# RDN.net
KiCad netlist of a schematic drawn in EAGLE
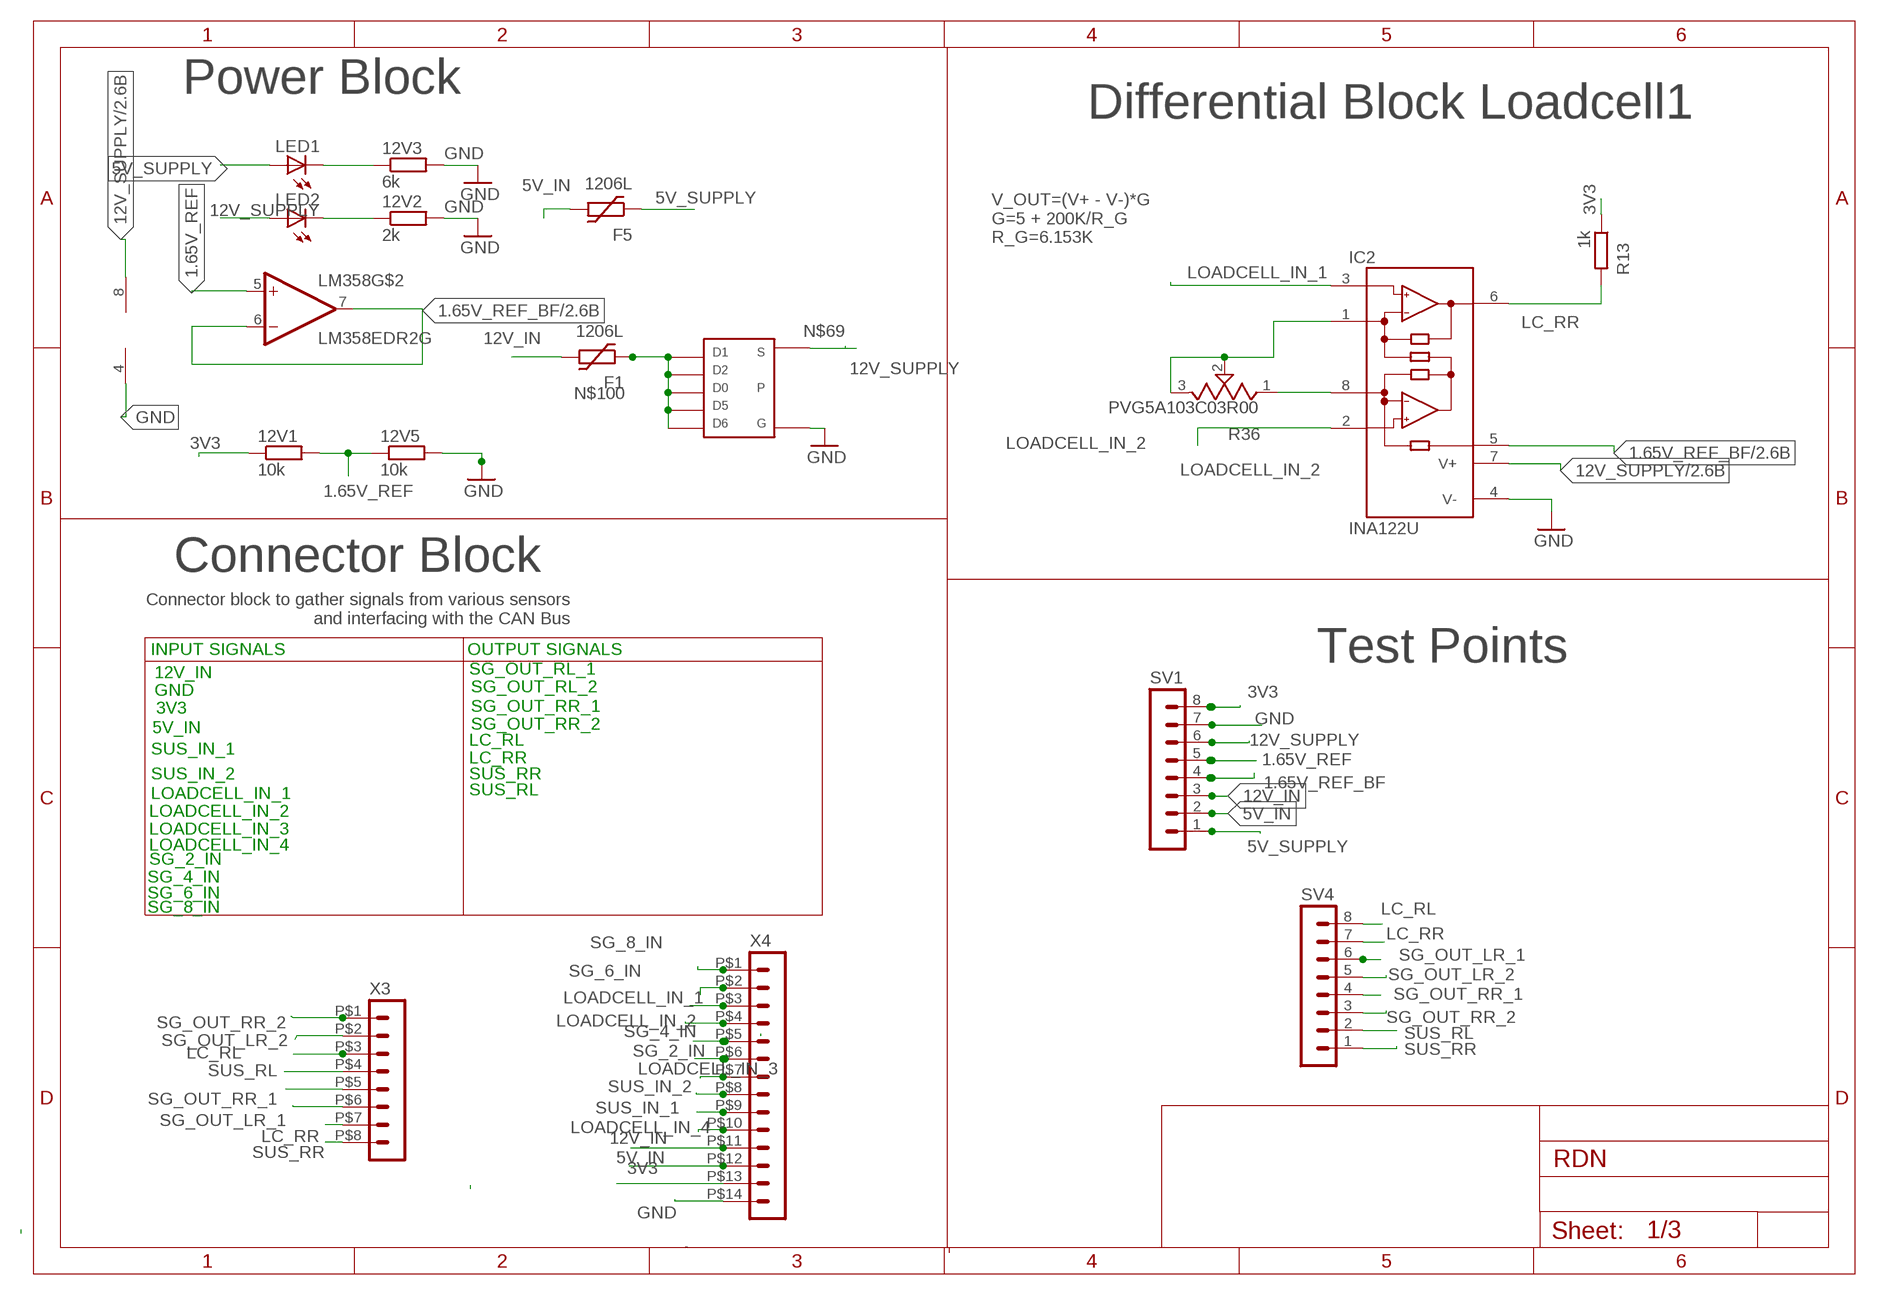
[diagram p0: schematic, sheet 1]
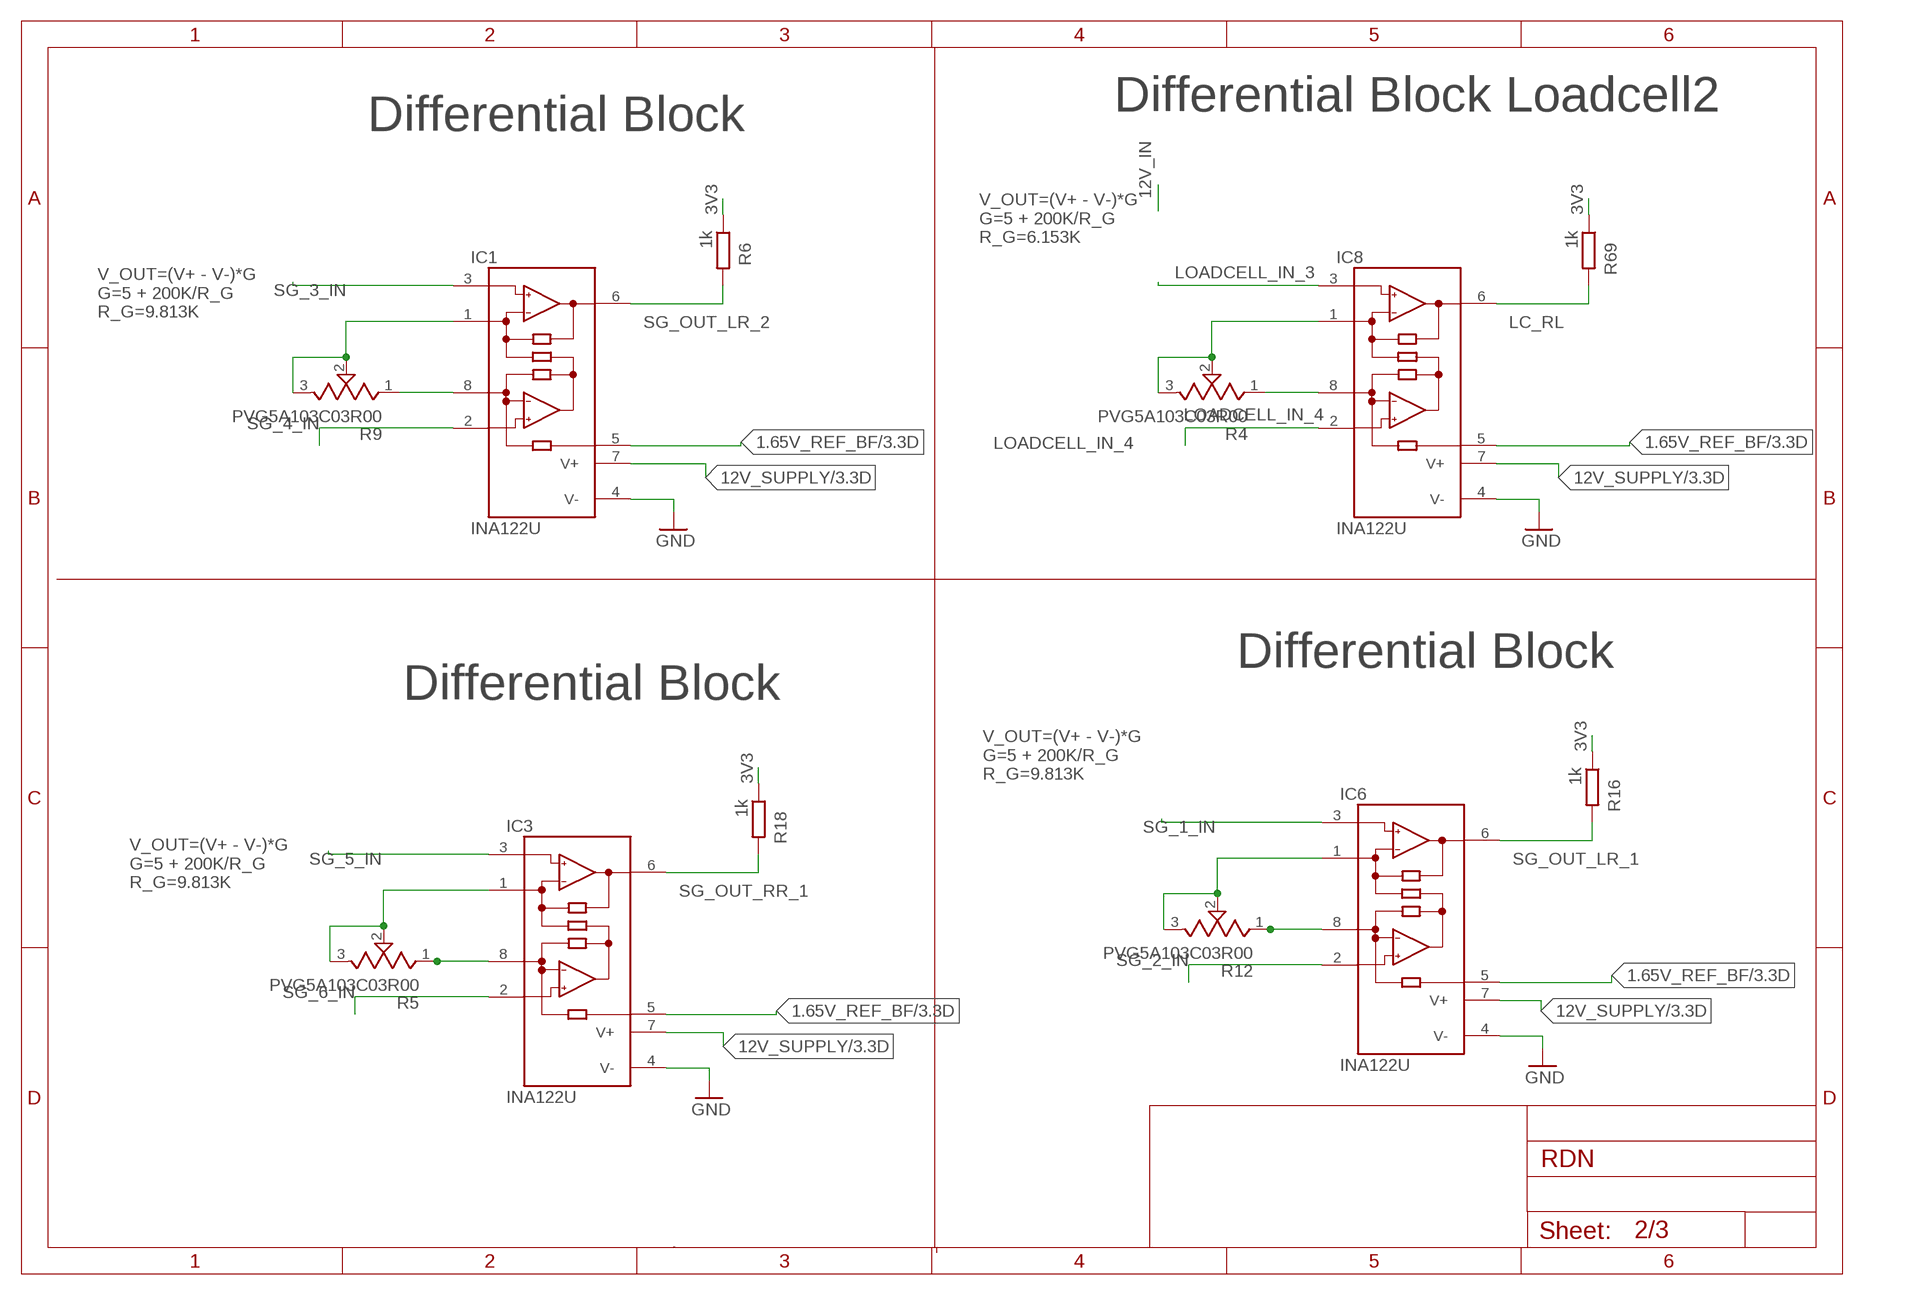
[diagram p1: schematic, sheet 2]
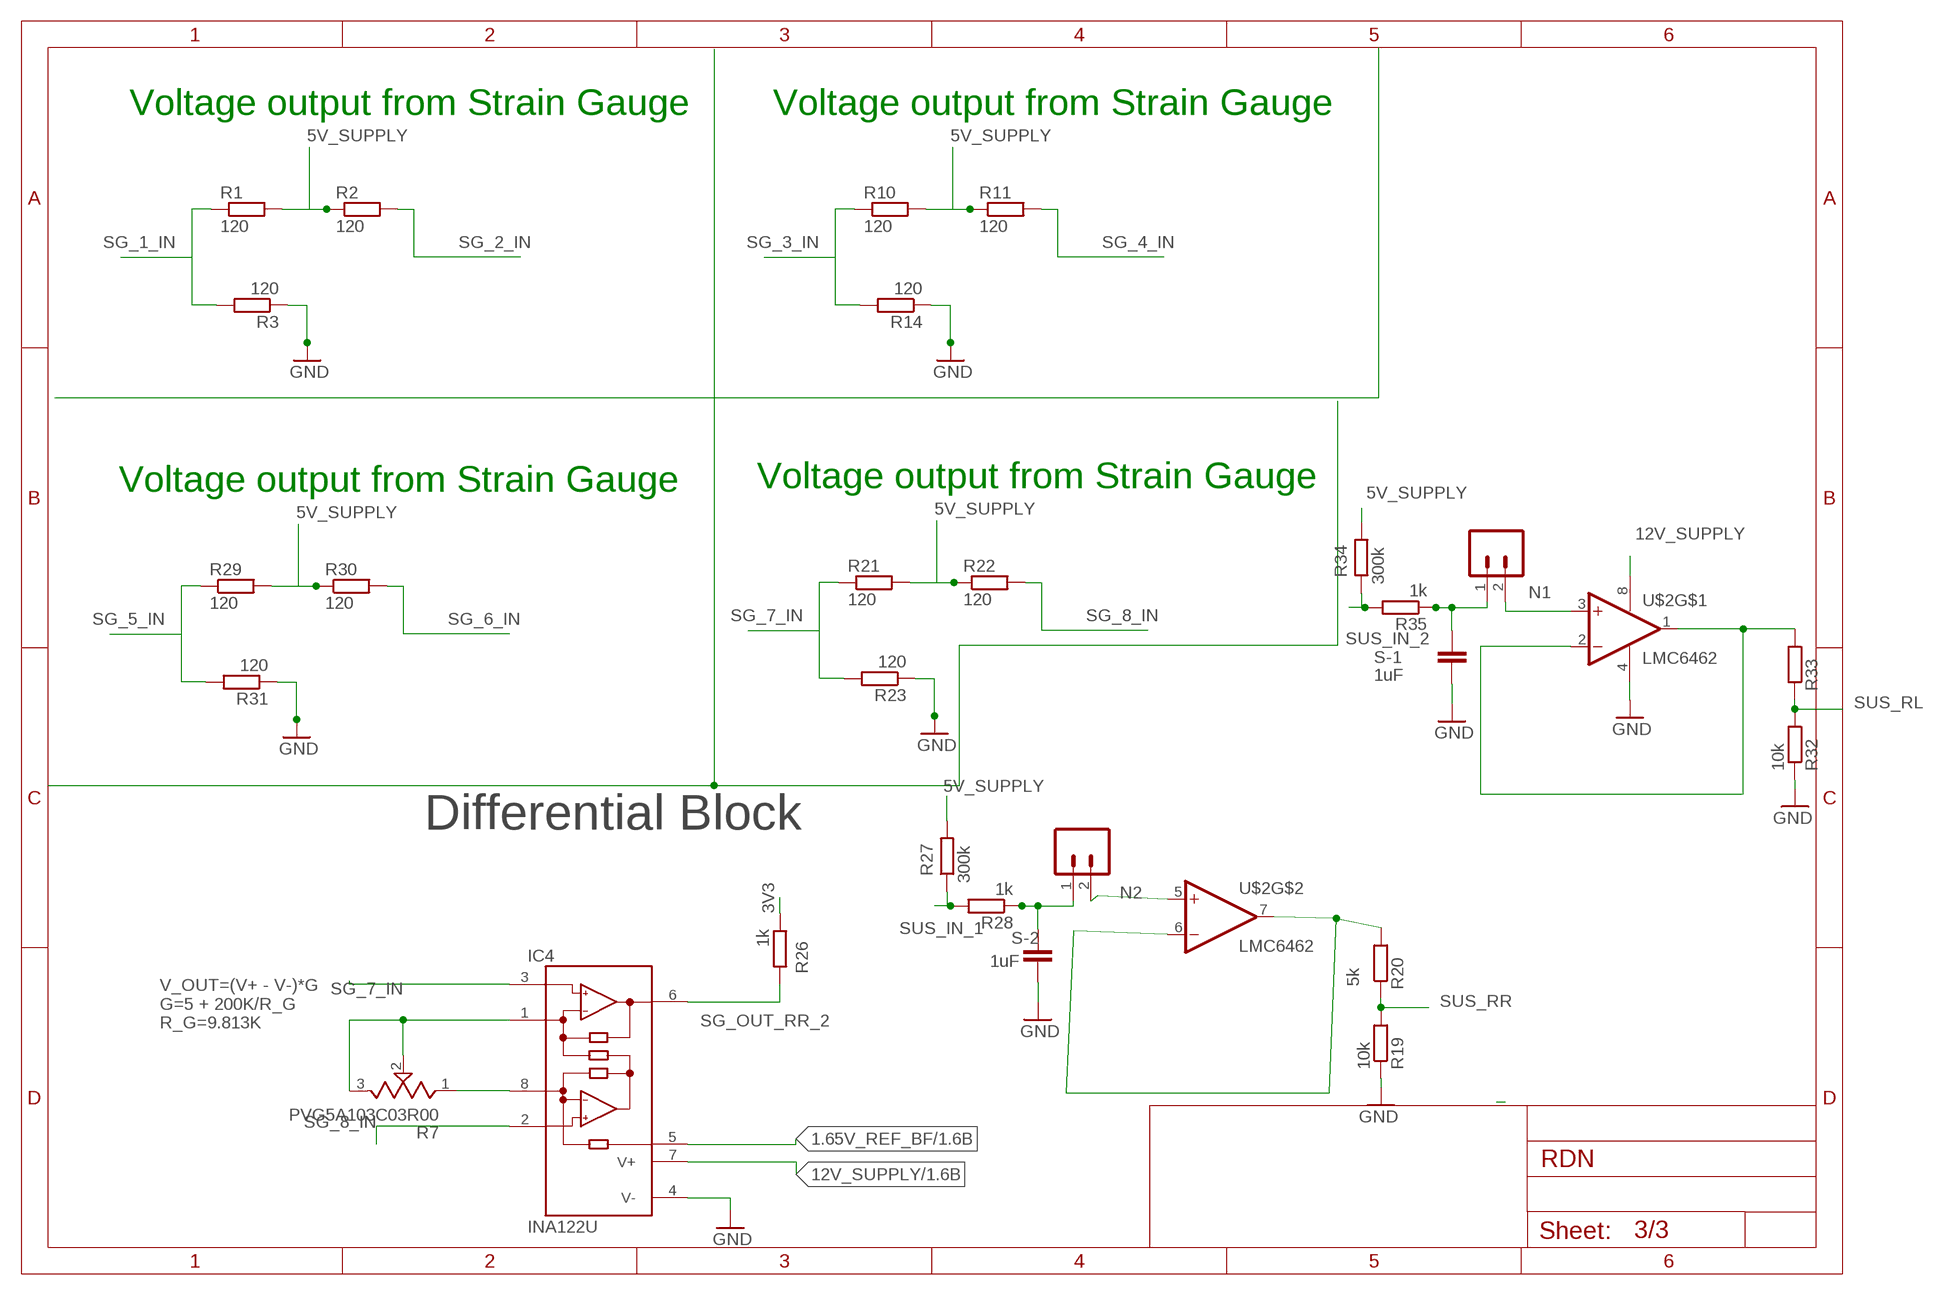
[diagram p2: schematic, sheet 3]

(export (version "E")
  (design (tool "Eeschema 10.0.6"))
  (components
    (comp (ref "IC4")
      (value "INA122U")
      (footprint "eagle-import:SO08")
      (libsource (lib "eagle-import") (part "INA122U"))
    )
    (comp (ref "R1")
      (value "120")
      (footprint "eagle-import:R0805")
      (libsource (lib "eagle-import") (part "rcl_R-EU_R0805"))
    )
    (comp (ref "R2")
      (value "120")
      (footprint "eagle-import:R0805")
      (libsource (lib "eagle-import") (part "rcl_R-EU_R0805"))
    )
    (comp (ref "R3")
      (value "120")
      (footprint "eagle-import:R0805")
      (libsource (lib "eagle-import") (part "rcl_R-EU_R0805"))
    )
    (comp (ref "R7")
      (value "PVG5A103C03R00")
      (footprint "eagle-import:TRIM_PVG5A103C03R00")
      (fields (field (name "MF") "Bourns"))
      (libsource (lib "eagle-import") (part "PVG5A103C03R00"))
    )
    (comp (ref "R10")
      (value "120")
      (footprint "eagle-import:R0805")
      (libsource (lib "eagle-import") (part "rcl_R-EU_R0805"))
    )
    (comp (ref "R11")
      (value "120")
      (footprint "eagle-import:R0805")
      (libsource (lib "eagle-import") (part "rcl_R-EU_R0805"))
    )
    (comp (ref "R14")
      (value "120")
      (footprint "eagle-import:R0805")
      (libsource (lib "eagle-import") (part "rcl_R-EU_R0805"))
    )
    (comp (ref "R19")
      (value "10k")
      (footprint "eagle-import:R0805")
      (libsource (lib "eagle-import") (part "IIT_BOMBAY_Racing2_R-EU_R0805"))
    )
    (comp (ref "R20")
      (value "5k")
      (footprint "eagle-import:R0805")
      (libsource (lib "eagle-import") (part "IIT_BOMBAY_Racing2_R-EU_R0805"))
    )
    (comp (ref "R21")
      (value "120")
      (footprint "eagle-import:R0805")
      (libsource (lib "eagle-import") (part "rcl_R-EU_R0805"))
    )
    (comp (ref "R22")
      (value "120")
      (footprint "eagle-import:R0805")
      (libsource (lib "eagle-import") (part "rcl_R-EU_R0805"))
    )
    (comp (ref "R23")
      (value "120")
      (footprint "eagle-import:R0805")
      (libsource (lib "eagle-import") (part "rcl_R-EU_R0805"))
    )
    (comp (ref "R26")
      (value "1k")
      (footprint "eagle-import:R0805")
      (libsource (lib "eagle-import") (part "R-EU_R0805"))
    )
    (comp (ref "R27")
      (value "300k")
      (footprint "eagle-import:R0805")
      (libsource (lib "eagle-import") (part "IIT_BOMBAY_Racing2_R-EU_R0805"))
    )
    (comp (ref "R28")
      (value "1k")
      (footprint "eagle-import:R0805")
      (libsource (lib "eagle-import") (part "IIT_BOMBAY_Racing2_R-EU_R0805"))
    )
    (comp (ref "R29")
      (value "120")
      (footprint "eagle-import:R0805")
      (libsource (lib "eagle-import") (part "rcl_R-EU_R0805"))
    )
    (comp (ref "R30")
      (value "120")
      (footprint "eagle-import:R0805")
      (libsource (lib "eagle-import") (part "rcl_R-EU_R0805"))
    )
    (comp (ref "R31")
      (value "120")
      (footprint "eagle-import:R0805")
      (libsource (lib "eagle-import") (part "rcl_R-EU_R0805"))
    )
    (comp (ref "R32")
      (value "10k")
      (footprint "eagle-import:R0805")
      (libsource (lib "eagle-import") (part "IIT_BOMBAY_Racing2_R-EU_R0805"))
    )
    (comp (ref "R33")
      (value "5k")
      (footprint "eagle-import:R0805")
      (libsource (lib "eagle-import") (part "IIT_BOMBAY_Racing2_R-EU_R0805"))
    )
    (comp (ref "R34")
      (value "300k")
      (footprint "eagle-import:R0805")
      (libsource (lib "eagle-import") (part "IIT_BOMBAY_Racing2_R-EU_R0805"))
    )
    (comp (ref "R35")
      (value "1k")
      (footprint "eagle-import:R0805")
      (libsource (lib "eagle-import") (part "IIT_BOMBAY_Racing2_R-EU_R0805"))
    )
    (comp (ref "S-1")
      (value "1uF")
      (footprint "eagle-import:C0805")
      (libsource (lib "eagle-import") (part "C-EUC0805"))
    )
    (comp (ref "S-2")
      (value "1uF")
      (footprint "eagle-import:C0805")
      (libsource (lib "eagle-import") (part "C-EUC0805"))
    )
    (comp (ref "STEERING_JP")
      (value "STEERING_JP")
      (footprint "eagle-import:1X02")
      (libsource (lib "eagle-import") (part "CONN_02"))
    )
    (comp (ref "STEERING_JP1")
      (value "STEERING_JP")
      (footprint "eagle-import:1X02")
      (libsource (lib "eagle-import") (part "CONN_02"))
    )
    (comp (ref "U$2")
      (value "LMC6462")
      (footprint "eagle-import:S08")
      (libsource (lib "eagle-import") (part "LMC6462"))
    )
    (comp (ref "IC1")
      (value "INA122U")
      (footprint "eagle-import:SO08")
      (libsource (lib "eagle-import") (part "INA122U"))
    )
    (comp (ref "IC3")
      (value "INA122U")
      (footprint "eagle-import:SO08")
      (libsource (lib "eagle-import") (part "INA122U"))
    )
    (comp (ref "IC6")
      (value "INA122U")
      (footprint "eagle-import:SO08")
      (libsource (lib "eagle-import") (part "INA122U"))
    )
    (comp (ref "IC8")
      (value "INA122U")
      (footprint "eagle-import:SO08")
      (libsource (lib "eagle-import") (part "INA122U"))
    )
    (comp (ref "R4")
      (value "PVG5A103C03R00")
      (footprint "eagle-import:TRIM_PVG5A103C03R00")
      (fields (field (name "MF") "Bourns"))
      (libsource (lib "eagle-import") (part "PVG5A103C03R00"))
    )
    (comp (ref "R5")
      (value "PVG5A103C03R00")
      (footprint "eagle-import:TRIM_PVG5A103C03R00")
      (fields (field (name "MF") "Bourns"))
      (libsource (lib "eagle-import") (part "PVG5A103C03R00"))
    )
    (comp (ref "R6")
      (value "1k")
      (footprint "eagle-import:R0805")
      (libsource (lib "eagle-import") (part "R-EU_R0805"))
    )
    (comp (ref "R9")
      (value "PVG5A103C03R00")
      (footprint "eagle-import:TRIM_PVG5A103C03R00")
      (fields (field (name "MF") "Bourns"))
      (libsource (lib "eagle-import") (part "PVG5A103C03R00"))
    )
    (comp (ref "R12")
      (value "PVG5A103C03R00")
      (footprint "eagle-import:TRIM_PVG5A103C03R00")
      (fields (field (name "MF") "Bourns"))
      (libsource (lib "eagle-import") (part "PVG5A103C03R00"))
    )
    (comp (ref "R16")
      (value "1k")
      (footprint "eagle-import:R0805")
      (libsource (lib "eagle-import") (part "R-EU_R0805"))
    )
    (comp (ref "R18")
      (value "1k")
      (footprint "eagle-import:R0805")
      (libsource (lib "eagle-import") (part "R-EU_R0805"))
    )
    (comp (ref "R69")
      (value "1k")
      (footprint "eagle-import:R0805")
      (libsource (lib "eagle-import") (part "R-EU_R0805"))
    )
    (comp (ref "12V1")
      (value "10k")
      (footprint "eagle-import:R0805")
      (libsource (lib "eagle-import") (part "rcl_R-EU_R0805"))
    )
    (comp (ref "12V2")
      (value "2k")
      (footprint "eagle-import:R0805")
      (libsource (lib "eagle-import") (part "rcl_R-EU_R0805"))
    )
    (comp (ref "12V3")
      (value "6k")
      (footprint "eagle-import:R0805")
      (libsource (lib "eagle-import") (part "rcl_R-EU_R0805"))
    )
    (comp (ref "12V5")
      (value "10k")
      (footprint "eagle-import:R0805")
      (libsource (lib "eagle-import") (part "rcl_R-EU_R0805"))
    )
    (comp (ref "F1")
      (value "1206L")
      (footprint "eagle-import:1206L")
      (libsource (lib "eagle-import") (part "1206L"))
    )
    (comp (ref "F5")
      (value "1206L")
      (footprint "eagle-import:1206L")
      (libsource (lib "eagle-import") (part "1206L"))
    )
    (comp (ref "IC2")
      (value "INA122U")
      (footprint "eagle-import:SO08")
      (libsource (lib "eagle-import") (part "INA122U"))
    )
    (comp (ref "LED1")
      (value "LEDCHIPLED_1206")
      (footprint "eagle-import:CHIPLED_1206")
      (libsource (lib "eagle-import") (part "LEDCHIPLED_1206"))
    )
    (comp (ref "LED2")
      (value "LEDCHIPLED_1206")
      (footprint "eagle-import:CHIPLED_1206")
      (fields (field (name "SPICEPREFIX") "L"))
      (libsource (lib "eagle-import") (part "LEDCHIPLED_1206"))
    )
    (comp (ref "LM358")
      (value "LM358EDR2G")
      (footprint "eagle-import:SOIC-8")
      (libsource (lib "eagle-import") (part "LM358EDR2G"))
    )
    (comp (ref "R13")
      (value "1k")
      (footprint "eagle-import:R0805")
      (libsource (lib "eagle-import") (part "R-EU_R0805"))
    )
    (comp (ref "R36")
      (value "PVG5A103C03R00")
      (footprint "eagle-import:TRIM_PVG5A103C03R00")
      (fields (field (name "MF") "Bourns"))
      (libsource (lib "eagle-import") (part "PVG5A103C03R00"))
    )
    (comp (ref "SV1")
      (value "MA08-1")
      (footprint "eagle-import:MA08-1")
      (libsource (lib "eagle-import") (part "MA08-1"))
    )
    (comp (ref "SV4")
      (value "MA08-1")
      (footprint "eagle-import:MA08-1")
      (libsource (lib "eagle-import") (part "MA08-1"))
    )
    (comp (ref "U$1")
      (value "TSOP-6_PMOS")
      (footprint "eagle-import:TSOP-6_PMOS")
      (libsource (lib "eagle-import") (part "TSOP-6_PMOS"))
    )
    (comp (ref "X3")
      (value "HEADER_POS8_44769-0801")
      (footprint "eagle-import:44769-0801")
      (libsource (lib "eagle-import") (part "HEADER_POS8_?44769-0801"))
    )
    (comp (ref "X4")
      (value "HEADER_POS14_44769-1401")
      (footprint "eagle-import:44769-1401")
      (libsource (lib "eagle-import") (part "HEADER_POS14_?44769-1401"))
    )
  )
  (nets
    (net (code "1") (name "1.65V_REF") (class "Default")
      (node (ref "12V1") (pin "2") (pinfunction "2_2") (pintype "passive"))
      (node (ref "12V5") (pin "1") (pinfunction "1_1") (pintype "passive"))
      (node (ref "LM358") (pin "5") (pinfunction "+IN_5") (pintype "input"))
      (node (ref "SV1") (pin "5") (pinfunction "5_5") (pintype "passive"))
    )
    (net (code "2") (name "1.65V_REF_BF") (class "Default")
      (node (ref "IC1") (pin "5") (pinfunction "REF_5") (pintype "passive"))
      (node (ref "IC2") (pin "5") (pinfunction "REF_5") (pintype "passive"))
      (node (ref "IC3") (pin "5") (pinfunction "REF_5") (pintype "passive"))
      (node (ref "IC4") (pin "5") (pinfunction "REF_5") (pintype "passive"))
      (node (ref "IC6") (pin "5") (pinfunction "REF_5") (pintype "passive"))
      (node (ref "IC8") (pin "5") (pinfunction "REF_5") (pintype "passive"))
      (node (ref "LM358") (pin "6") (pinfunction "-IN_6") (pintype "input"))
      (node (ref "LM358") (pin "7") (pinfunction "OUT_7") (pintype "output"))
      (node (ref "SV1") (pin "4") (pinfunction "4_4") (pintype "passive"))
    )
    (net (code "3") (name "3V3") (class "Default")
      (node (ref "12V1") (pin "1") (pinfunction "1_1") (pintype "passive"))
      (node (ref "R13") (pin "1") (pinfunction "1_1") (pintype "passive"))
      (node (ref "R16") (pin "1") (pinfunction "1_1") (pintype "passive"))
      (node (ref "R18") (pin "1") (pinfunction "1_1") (pintype "passive"))
      (node (ref "R26") (pin "1") (pinfunction "1_1") (pintype "passive"))
      (node (ref "R6") (pin "1") (pinfunction "1_1") (pintype "passive"))
      (node (ref "R69") (pin "1") (pinfunction "1_1") (pintype "passive"))
      (node (ref "SV1") (pin "8") (pinfunction "8_8") (pintype "passive"))
      (node (ref "X4") (pin "P$13") (pinfunction "13_P$13") (pintype "passive"))
    )
    (net (code "4") (name "5V_IN") (class "Default")
      (node (ref "F5") (pin "P$2") (pinfunction "2_P$2") (pintype "passive"))
      (node (ref "SV1") (pin "2") (pinfunction "2_2") (pintype "passive"))
      (node (ref "X4") (pin "P$12") (pinfunction "12_P$12") (pintype "passive"))
    )
    (net (code "5") (name "5V_SUPPLY") (class "Default")
      (node (ref "F5") (pin "P$1") (pinfunction "1_P$1") (pintype "passive"))
      (node (ref "LED1") (pin "A") (pinfunction "A_A") (pintype "passive"))
      (node (ref "R1") (pin "2") (pinfunction "2_2") (pintype "passive"))
      (node (ref "R10") (pin "2") (pinfunction "2_2") (pintype "passive"))
      (node (ref "R11") (pin "1") (pinfunction "1_1") (pintype "passive"))
      (node (ref "R2") (pin "1") (pinfunction "1_1") (pintype "passive"))
      (node (ref "R21") (pin "2") (pinfunction "2_2") (pintype "passive"))
      (node (ref "R22") (pin "1") (pinfunction "1_1") (pintype "passive"))
      (node (ref "R27") (pin "2") (pinfunction "2_2") (pintype "passive"))
      (node (ref "R29") (pin "2") (pinfunction "2_2") (pintype "passive"))
      (node (ref "R30") (pin "1") (pinfunction "1_1") (pintype "passive"))
      (node (ref "R34") (pin "2") (pinfunction "2_2") (pintype "passive"))
      (node (ref "SV1") (pin "1") (pinfunction "1_1") (pintype "passive"))
    )
    (net (code "6") (name "12V_IN") (class "Default")
      (node (ref "F1") (pin "P$2") (pinfunction "2_P$2") (pintype "passive"))
      (node (ref "SV1") (pin "3") (pinfunction "3_3") (pintype "passive"))
      (node (ref "X4") (pin "P$11") (pinfunction "11_P$11") (pintype "passive"))
    )
    (net (code "7") (name "12V_SUPPLY") (class "Default")
      (node (ref "IC1") (pin "7") (pinfunction "V+_7") (pintype "power_in"))
      (node (ref "IC2") (pin "7") (pinfunction "V+_7") (pintype "power_in"))
      (node (ref "IC3") (pin "7") (pinfunction "V+_7") (pintype "power_in"))
      (node (ref "IC4") (pin "7") (pinfunction "V+_7") (pintype "power_in"))
      (node (ref "IC6") (pin "7") (pinfunction "V+_7") (pintype "power_in"))
      (node (ref "IC8") (pin "7") (pinfunction "V+_7") (pintype "power_in"))
      (node (ref "LED2") (pin "A") (pinfunction "A_A") (pintype "passive"))
      (node (ref "LM358") (pin "8") (pinfunction "V+_8") (pintype "power_in"))
      (node (ref "SV1") (pin "6") (pinfunction "6_6") (pintype "passive"))
      (node (ref "U$1") (pin "S") (pinfunction "S_S") (pintype "bidirectional"))
      (node (ref "U$2") (pin "8") (pinfunction "V+_8") (pintype "power_in"))
    )
    (net (code "8") (name "GND") (class "Default")
      (node (ref "12V2") (pin "2") (pinfunction "2_2") (pintype "passive"))
      (node (ref "12V3") (pin "2") (pinfunction "2_2") (pintype "passive"))
      (node (ref "12V5") (pin "2") (pinfunction "2_2") (pintype "passive"))
      (node (ref "IC1") (pin "4") (pinfunction "V-_4") (pintype "power_in"))
      (node (ref "IC2") (pin "4") (pinfunction "V-_4") (pintype "power_in"))
      (node (ref "IC3") (pin "4") (pinfunction "V-_4") (pintype "power_in"))
      (node (ref "IC4") (pin "4") (pinfunction "V-_4") (pintype "power_in"))
      (node (ref "IC6") (pin "4") (pinfunction "V-_4") (pintype "power_in"))
      (node (ref "IC8") (pin "4") (pinfunction "V-_4") (pintype "power_in"))
      (node (ref "LM358") (pin "4") (pinfunction "V-_4") (pintype "power_in"))
      (node (ref "R14") (pin "1") (pinfunction "1_1") (pintype "passive"))
      (node (ref "R19") (pin "1") (pinfunction "1_1") (pintype "passive"))
      (node (ref "R23") (pin "1") (pinfunction "1_1") (pintype "passive"))
      (node (ref "R3") (pin "1") (pinfunction "1_1") (pintype "passive"))
      (node (ref "R31") (pin "1") (pinfunction "1_1") (pintype "passive"))
      (node (ref "R32") (pin "1") (pinfunction "1_1") (pintype "passive"))
      (node (ref "S-1") (pin "2") (pinfunction "2_2") (pintype "passive"))
      (node (ref "S-2") (pin "2") (pinfunction "2_2") (pintype "passive"))
      (node (ref "SV1") (pin "7") (pinfunction "7_7") (pintype "passive"))
      (node (ref "U$1") (pin "G") (pinfunction "G_G") (pintype "bidirectional"))
      (node (ref "U$2") (pin "4") (pinfunction "V-_4") (pintype "power_in"))
      (node (ref "X4") (pin "P$14") (pinfunction "14_P$14") (pintype "passive"))
    )
    (net (code "9") (name "LC_RL") (class "Default")
      (node (ref "IC8") (pin "6") (pinfunction "OUT_6") (pintype "output"))
      (node (ref "R69") (pin "2") (pinfunction "2_2") (pintype "passive"))
      (node (ref "SV4") (pin "8") (pinfunction "8_8") (pintype "passive"))
      (node (ref "X3") (pin "P$3") (pinfunction "3_P$3") (pintype "passive"))
    )
    (net (code "10") (name "LC_RR") (class "Default")
      (node (ref "IC2") (pin "6") (pinfunction "OUT_6") (pintype "output"))
      (node (ref "R13") (pin "2") (pinfunction "2_2") (pintype "passive"))
      (node (ref "SV4") (pin "7") (pinfunction "7_7") (pintype "passive"))
      (node (ref "X3") (pin "P$7") (pinfunction "7_P$7") (pintype "passive"))
    )
    (net (code "11") (name "LOADCELL_IN_1") (class "Default")
      (node (ref "IC2") (pin "3") (pinfunction "+IN_3") (pintype "input"))
      (node (ref "X4") (pin "P$3") (pinfunction "3_P$3") (pintype "passive"))
    )
    (net (code "12") (name "LOADCELL_IN_2") (class "Default")
      (node (ref "IC2") (pin "2") (pinfunction "-IN_2") (pintype "input"))
      (node (ref "X4") (pin "P$4") (pinfunction "4_P$4") (pintype "passive"))
    )
    (net (code "13") (name "LOADCELL_IN_3") (class "Default")
      (node (ref "IC8") (pin "3") (pinfunction "+IN_3") (pintype "input"))
      (node (ref "X4") (pin "P$7") (pinfunction "7_P$7") (pintype "passive"))
    )
    (net (code "14") (name "LOADCELL_IN_4") (class "Default")
      (node (ref "IC8") (pin "2") (pinfunction "-IN_2") (pintype "input"))
      (node (ref "X4") (pin "P$10") (pinfunction "10_P$10") (pintype "passive"))
    )
    (net (code "16") (name "N$100") (class "Default")
      (node (ref "F1") (pin "P$1") (pinfunction "1_P$1") (pintype "passive"))
      (node (ref "U$1") (pin "1") (pinfunction "1_1") (pintype "bidirectional"))
      (node (ref "U$1") (pin "2") (pinfunction "2_2") (pintype "bidirectional"))
      (node (ref "U$1") (pin "5") (pinfunction "5_5") (pintype "bidirectional"))
      (node (ref "U$1") (pin "6") (pinfunction "6_6") (pintype "bidirectional"))
      (node (ref "U$1") (pin "D") (pinfunction "D0_D") (pintype "bidirectional"))
    )
    (net (code "17") (name "N1") (class "Default")
      (node (ref "STEERING_JP1") (pin "2") (pinfunction "2_2") (pintype "passive"))
      (node (ref "U$2") (pin "3") (pinfunction "+IN_3") (pintype "input"))
    )
    (net (code "18") (name "N2") (class "Default")
      (node (ref "STEERING_JP") (pin "2") (pinfunction "2_2") (pintype "passive"))
      (node (ref "U$2") (pin "5") (pinfunction "+IN_5") (pintype "input"))
    )
    (net (code "19") (name "Net-(12V2-Pad1)") (class "Default")
      (node (ref "12V2") (pin "1") (pinfunction "1_1") (pintype "passive"))
      (node (ref "LED2") (pin "C") (pinfunction "C_C") (pintype "passive"))
    )
    (net (code "20") (name "Net-(12V3-Pad1)") (class "Default")
      (node (ref "12V3") (pin "1") (pinfunction "1_1") (pintype "passive"))
      (node (ref "LED1") (pin "C") (pinfunction "C_C") (pintype "passive"))
    )
    (net (code "21") (name "Net-(IC1-RG-Pad1)") (class "Default")
      (node (ref "IC1") (pin "1") (pinfunction "RG_1") (pintype "passive"))
      (node (ref "R9") (pin "2") (pinfunction "2_2") (pintype "passive"))
      (node (ref "R9") (pin "3") (pinfunction "3_3") (pintype "passive"))
    )
    (net (code "22") (name "Net-(IC1-RG-Pad8)") (class "Default")
      (node (ref "IC1") (pin "8") (pinfunction "RG_8") (pintype "passive"))
      (node (ref "R9") (pin "1") (pinfunction "1_1") (pintype "passive"))
    )
    (net (code "23") (name "Net-(IC2-RG-Pad1)") (class "Default")
      (node (ref "IC2") (pin "1") (pinfunction "RG_1") (pintype "passive"))
      (node (ref "R36") (pin "2") (pinfunction "2_2") (pintype "passive"))
      (node (ref "R36") (pin "3") (pinfunction "3_3") (pintype "passive"))
    )
    (net (code "24") (name "Net-(IC2-RG-Pad8)") (class "Default")
      (node (ref "IC2") (pin "8") (pinfunction "RG_8") (pintype "passive"))
      (node (ref "R36") (pin "1") (pinfunction "1_1") (pintype "passive"))
    )
    (net (code "25") (name "Net-(IC3-RG-Pad1)") (class "Default")
      (node (ref "IC3") (pin "1") (pinfunction "RG_1") (pintype "passive"))
      (node (ref "R5") (pin "2") (pinfunction "2_2") (pintype "passive"))
      (node (ref "R5") (pin "3") (pinfunction "3_3") (pintype "passive"))
    )
    (net (code "26") (name "Net-(IC3-RG-Pad8)") (class "Default")
      (node (ref "IC3") (pin "8") (pinfunction "RG_8") (pintype "passive"))
      (node (ref "R5") (pin "1") (pinfunction "1_1") (pintype "passive"))
    )
    (net (code "27") (name "Net-(IC4-RG-Pad1)") (class "Default")
      (node (ref "IC4") (pin "1") (pinfunction "RG_1") (pintype "passive"))
      (node (ref "R7") (pin "2") (pinfunction "2_2") (pintype "passive"))
      (node (ref "R7") (pin "3") (pinfunction "3_3") (pintype "passive"))
    )
    (net (code "28") (name "Net-(IC4-RG-Pad8)") (class "Default")
      (node (ref "IC4") (pin "8") (pinfunction "RG_8") (pintype "passive"))
      (node (ref "R7") (pin "1") (pinfunction "1_1") (pintype "passive"))
    )
    (net (code "29") (name "Net-(IC6-RG-Pad1)") (class "Default")
      (node (ref "IC6") (pin "1") (pinfunction "RG_1") (pintype "passive"))
      (node (ref "R12") (pin "2") (pinfunction "2_2") (pintype "passive"))
      (node (ref "R12") (pin "3") (pinfunction "3_3") (pintype "passive"))
    )
    (net (code "30") (name "Net-(IC6-RG-Pad8)") (class "Default")
      (node (ref "IC6") (pin "8") (pinfunction "RG_8") (pintype "passive"))
      (node (ref "R12") (pin "1") (pinfunction "1_1") (pintype "passive"))
    )
    (net (code "31") (name "Net-(IC8-RG-Pad1)") (class "Default")
      (node (ref "IC8") (pin "1") (pinfunction "RG_1") (pintype "passive"))
      (node (ref "R4") (pin "2") (pinfunction "2_2") (pintype "passive"))
      (node (ref "R4") (pin "3") (pinfunction "3_3") (pintype "passive"))
    )
    (net (code "32") (name "Net-(IC8-RG-Pad8)") (class "Default")
      (node (ref "IC8") (pin "8") (pinfunction "RG_8") (pintype "passive"))
      (node (ref "R4") (pin "1") (pinfunction "1_1") (pintype "passive"))
    )
    (net (code "33") (name "Net-(R28-Pad1)") (class "Default")
      (node (ref "R28") (pin "1") (pinfunction "1_1") (pintype "passive"))
      (node (ref "S-2") (pin "1") (pinfunction "1_1") (pintype "passive"))
      (node (ref "STEERING_JP") (pin "1") (pinfunction "1_1") (pintype "passive"))
    )
    (net (code "34") (name "Net-(R35-Pad1)") (class "Default")
      (node (ref "R35") (pin "1") (pinfunction "1_1") (pintype "passive"))
      (node (ref "S-1") (pin "1") (pinfunction "1_1") (pintype "passive"))
      (node (ref "STEERING_JP1") (pin "1") (pinfunction "1_1") (pintype "passive"))
    )
    (net (code "35") (name "Net-(U$2A--IN)") (class "Default")
      (node (ref "R33") (pin "2") (pinfunction "2_2") (pintype "passive"))
      (node (ref "U$2") (pin "1") (pinfunction "OUT_1") (pintype "output"))
      (node (ref "U$2") (pin "2") (pinfunction "-IN_2") (pintype "input"))
    )
    (net (code "36") (name "Net-(U$2B--IN)") (class "Default")
      (node (ref "R20") (pin "2") (pinfunction "2_2") (pintype "passive"))
      (node (ref "U$2") (pin "6") (pinfunction "-IN_6") (pintype "input"))
      (node (ref "U$2") (pin "7") (pinfunction "OUT_7") (pintype "output"))
    )
    (net (code "37") (name "SG_1_IN") (class "Default")
      (node (ref "IC6") (pin "3") (pinfunction "+IN_3") (pintype "input"))
      (node (ref "R1") (pin "1") (pinfunction "1_1") (pintype "passive"))
      (node (ref "R3") (pin "2") (pinfunction "2_2") (pintype "passive"))
    )
    (net (code "38") (name "SG_2_IN") (class "Default")
      (node (ref "IC6") (pin "2") (pinfunction "-IN_2") (pintype "input"))
      (node (ref "R2") (pin "2") (pinfunction "2_2") (pintype "passive"))
      (node (ref "X4") (pin "P$6") (pinfunction "6_P$6") (pintype "passive"))
    )
    (net (code "39") (name "SG_3_IN") (class "Default")
      (node (ref "IC1") (pin "3") (pinfunction "+IN_3") (pintype "input"))
      (node (ref "R10") (pin "1") (pinfunction "1_1") (pintype "passive"))
      (node (ref "R14") (pin "2") (pinfunction "2_2") (pintype "passive"))
    )
    (net (code "40") (name "SG_4_IN") (class "Default")
      (node (ref "IC1") (pin "2") (pinfunction "-IN_2") (pintype "input"))
      (node (ref "R11") (pin "2") (pinfunction "2_2") (pintype "passive"))
      (node (ref "X4") (pin "P$5") (pinfunction "5_P$5") (pintype "passive"))
    )
    (net (code "41") (name "SG_5_IN") (class "Default")
      (node (ref "IC3") (pin "3") (pinfunction "+IN_3") (pintype "input"))
      (node (ref "R29") (pin "1") (pinfunction "1_1") (pintype "passive"))
      (node (ref "R31") (pin "2") (pinfunction "2_2") (pintype "passive"))
    )
    (net (code "42") (name "SG_6_IN") (class "Default")
      (node (ref "IC3") (pin "2") (pinfunction "-IN_2") (pintype "input"))
      (node (ref "R30") (pin "2") (pinfunction "2_2") (pintype "passive"))
      (node (ref "X4") (pin "P$2") (pinfunction "2_P$2") (pintype "passive"))
    )
    (net (code "43") (name "SG_7_IN") (class "Default")
      (node (ref "IC4") (pin "3") (pinfunction "+IN_3") (pintype "input"))
      (node (ref "R21") (pin "1") (pinfunction "1_1") (pintype "passive"))
      (node (ref "R23") (pin "2") (pinfunction "2_2") (pintype "passive"))
    )
    (net (code "44") (name "SG_8_IN") (class "Default")
      (node (ref "IC4") (pin "2") (pinfunction "-IN_2") (pintype "input"))
      (node (ref "R22") (pin "2") (pinfunction "2_2") (pintype "passive"))
      (node (ref "X4") (pin "P$1") (pinfunction "1_P$1") (pintype "passive"))
    )
    (net (code "45") (name "SG_OUT_LR_1") (class "Default")
      (node (ref "IC6") (pin "6") (pinfunction "OUT_6") (pintype "output"))
      (node (ref "R16") (pin "2") (pinfunction "2_2") (pintype "passive"))
      (node (ref "SV4") (pin "6") (pinfunction "6_6") (pintype "passive"))
      (node (ref "X3") (pin "P$6") (pinfunction "6_P$6") (pintype "passive"))
    )
    (net (code "46") (name "SG_OUT_LR_2") (class "Default")
      (node (ref "IC1") (pin "6") (pinfunction "OUT_6") (pintype "output"))
      (node (ref "R6") (pin "2") (pinfunction "2_2") (pintype "passive"))
      (node (ref "SV4") (pin "5") (pinfunction "5_5") (pintype "passive"))
      (node (ref "X3") (pin "P$2") (pinfunction "2_P$2") (pintype "passive"))
    )
    (net (code "47") (name "SG_OUT_RR_1") (class "Default")
      (node (ref "IC3") (pin "6") (pinfunction "OUT_6") (pintype "output"))
      (node (ref "R18") (pin "2") (pinfunction "2_2") (pintype "passive"))
      (node (ref "SV4") (pin "4") (pinfunction "4_4") (pintype "passive"))
      (node (ref "X3") (pin "P$5") (pinfunction "5_P$5") (pintype "passive"))
    )
    (net (code "48") (name "SG_OUT_RR_2") (class "Default")
      (node (ref "IC4") (pin "6") (pinfunction "OUT_6") (pintype "output"))
      (node (ref "R26") (pin "2") (pinfunction "2_2") (pintype "passive"))
      (node (ref "SV4") (pin "3") (pinfunction "3_3") (pintype "passive"))
      (node (ref "X3") (pin "P$1") (pinfunction "1_P$1") (pintype "passive"))
    )
    (net (code "49") (name "SUS_IN_1") (class "Default")
      (node (ref "R27") (pin "1") (pinfunction "1_1") (pintype "passive"))
      (node (ref "R28") (pin "2") (pinfunction "2_2") (pintype "passive"))
      (node (ref "X4") (pin "P$9") (pinfunction "9_P$9") (pintype "passive"))
    )
    (net (code "50") (name "SUS_IN_2") (class "Default")
      (node (ref "R34") (pin "1") (pinfunction "1_1") (pintype "passive"))
      (node (ref "R35") (pin "2") (pinfunction "2_2") (pintype "passive"))
      (node (ref "X4") (pin "P$8") (pinfunction "8_P$8") (pintype "passive"))
    )
    (net (code "51") (name "SUS_RL") (class "Default")
      (node (ref "R32") (pin "2") (pinfunction "2_2") (pintype "passive"))
      (node (ref "R33") (pin "1") (pinfunction "1_1") (pintype "passive"))
      (node (ref "SV4") (pin "2") (pinfunction "2_2") (pintype "passive"))
      (node (ref "X3") (pin "P$4") (pinfunction "4_P$4") (pintype "passive"))
    )
    (net (code "52") (name "SUS_RR") (class "Default")
      (node (ref "R19") (pin "2") (pinfunction "2_2") (pintype "passive"))
      (node (ref "R20") (pin "1") (pinfunction "1_1") (pintype "passive"))
      (node (ref "SV4") (pin "1") (pinfunction "1_1") (pintype "passive"))
      (node (ref "X3") (pin "P$8") (pinfunction "8_P$8") (pintype "passive"))
    )
  )
)
